# Sheet1.net
KiCad netlist of a schematic drawn in Altium Designer
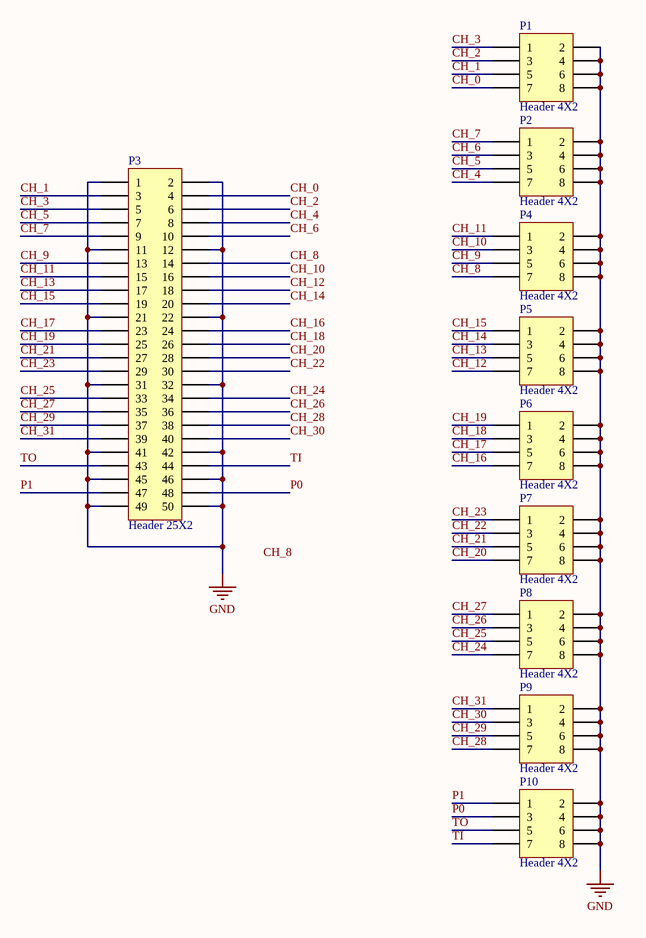
[diagram p0: Sheet1.SchDoc]

(export (version "E")
  (design (tool "Eeschema 10.0.6"))
  (components
    (comp (ref "P1")
      (value "Header 4X2")
      (footprint "HDR-2*4-1.27-SMD")
      (description "Header, 4-Pin, Dual row")
      (fields (field (name "PUBLISHER") "Altium Limited"))
      (libsource (lib "Miscellaneous Connectors") (part "Header 4X2"))
    )
    (comp (ref "P2")
      (value "Header 4X2")
      (footprint "HDR-2*4-1.27-SMD")
      (description "Header, 4-Pin, Dual row")
      (fields (field (name "PUBLISHER") "Altium Limited"))
      (libsource (lib "Miscellaneous Connectors") (part "Header 4X2"))
    )
    (comp (ref "P3")
      (value "Header 25X2")
      (footprint "HDR-2*25-2.54-SMD")
      (description "Header, 25-Pin, Dual row")
      (fields (field (name "PUBLISHER") "Altium Limited"))
      (libsource (lib "Miscellaneous Connectors") (part "Header 25X2"))
    )
    (comp (ref "P4")
      (value "Header 4X2")
      (footprint "HDR-2*4-1.27-SMD")
      (description "Header, 4-Pin, Dual row")
      (fields (field (name "PUBLISHER") "Altium Limited"))
      (libsource (lib "Miscellaneous Connectors") (part "Header 4X2"))
    )
    (comp (ref "P5")
      (value "Header 4X2")
      (footprint "HDR-2*4-1.27-SMD")
      (description "Header, 4-Pin, Dual row")
      (fields (field (name "PUBLISHER") "Altium Limited"))
      (libsource (lib "Miscellaneous Connectors") (part "Header 4X2"))
    )
    (comp (ref "P6")
      (value "Header 4X2")
      (footprint "HDR-2*4-1.27-SMD")
      (description "Header, 4-Pin, Dual row")
      (fields (field (name "PUBLISHER") "Altium Limited"))
      (libsource (lib "Miscellaneous Connectors") (part "Header 4X2"))
    )
    (comp (ref "P7")
      (value "Header 4X2")
      (footprint "HDR-2*4-1.27-SMD")
      (description "Header, 4-Pin, Dual row")
      (fields (field (name "PUBLISHER") "Altium Limited"))
      (libsource (lib "Miscellaneous Connectors") (part "Header 4X2"))
    )
    (comp (ref "P8")
      (value "Header 4X2")
      (footprint "HDR-2*4-1.27-SMD")
      (description "Header, 4-Pin, Dual row")
      (fields (field (name "PUBLISHER") "Altium Limited"))
      (libsource (lib "Miscellaneous Connectors") (part "Header 4X2"))
    )
    (comp (ref "P9")
      (value "Header 4X2")
      (footprint "HDR-2*4-1.27-SMD")
      (description "Header, 4-Pin, Dual row")
      (fields (field (name "PUBLISHER") "Altium Limited"))
      (libsource (lib "Miscellaneous Connectors") (part "Header 4X2"))
    )
    (comp (ref "P10")
      (value "Header 4X2")
      (footprint "HDR-2*4-1.27-SMD")
      (description "Header, 4-Pin, Dual row")
      (fields (field (name "PUBLISHER") "Altium Limited"))
      (libsource (lib "Miscellaneous Connectors") (part "Header 4X2"))
    )
  )
  (nets
    (net (code "1") (name "/CH_0") (class "Default")
      (node (ref "P1") (pin "7") (pinfunction "7_7") (pintype "passive"))
      (node (ref "P3") (pin "4") (pinfunction "4_4") (pintype "passive"))
    )
    (net (code "2") (name "/CH_1") (class "Default")
      (node (ref "P1") (pin "5") (pinfunction "5_5") (pintype "passive"))
      (node (ref "P3") (pin "3") (pinfunction "3_3") (pintype "passive"))
    )
    (net (code "3") (name "/CH_2") (class "Default")
      (node (ref "P1") (pin "3") (pinfunction "3_3") (pintype "passive"))
      (node (ref "P3") (pin "6") (pinfunction "6_6") (pintype "passive"))
    )
    (net (code "4") (name "/CH_3") (class "Default")
      (node (ref "P1") (pin "1") (pinfunction "1_1") (pintype "passive"))
      (node (ref "P3") (pin "5") (pinfunction "5_5") (pintype "passive"))
    )
    (net (code "5") (name "/CH_4") (class "Default")
      (node (ref "P2") (pin "7") (pinfunction "7_7") (pintype "passive"))
      (node (ref "P3") (pin "8") (pinfunction "8_8") (pintype "passive"))
    )
    (net (code "6") (name "/CH_5") (class "Default")
      (node (ref "P2") (pin "5") (pinfunction "5_5") (pintype "passive"))
      (node (ref "P3") (pin "7") (pinfunction "7_7") (pintype "passive"))
    )
    (net (code "7") (name "/CH_6") (class "Default")
      (node (ref "P2") (pin "3") (pinfunction "3_3") (pintype "passive"))
      (node (ref "P3") (pin "10") (pinfunction "10_10") (pintype "passive"))
    )
    (net (code "8") (name "/CH_7") (class "Default")
      (node (ref "P2") (pin "1") (pinfunction "1_1") (pintype "passive"))
      (node (ref "P3") (pin "9") (pinfunction "9_9") (pintype "passive"))
    )
    (net (code "9") (name "/CH_8") (class "Default")
      (node (ref "P3") (pin "14") (pinfunction "14_14") (pintype "passive"))
      (node (ref "P4") (pin "7") (pinfunction "7_7") (pintype "passive"))
    )
    (net (code "10") (name "/CH_9") (class "Default")
      (node (ref "P3") (pin "13") (pinfunction "13_13") (pintype "passive"))
      (node (ref "P4") (pin "5") (pinfunction "5_5") (pintype "passive"))
    )
    (net (code "11") (name "/CH_10") (class "Default")
      (node (ref "P3") (pin "16") (pinfunction "16_16") (pintype "passive"))
      (node (ref "P4") (pin "3") (pinfunction "3_3") (pintype "passive"))
    )
    (net (code "12") (name "/CH_11") (class "Default")
      (node (ref "P3") (pin "15") (pinfunction "15_15") (pintype "passive"))
      (node (ref "P4") (pin "1") (pinfunction "1_1") (pintype "passive"))
    )
    (net (code "13") (name "/CH_12") (class "Default")
      (node (ref "P3") (pin "18") (pinfunction "18_18") (pintype "passive"))
      (node (ref "P5") (pin "7") (pinfunction "7_7") (pintype "passive"))
    )
    (net (code "14") (name "/CH_13") (class "Default")
      (node (ref "P3") (pin "17") (pinfunction "17_17") (pintype "passive"))
      (node (ref "P5") (pin "5") (pinfunction "5_5") (pintype "passive"))
    )
    (net (code "15") (name "/CH_14") (class "Default")
      (node (ref "P3") (pin "20") (pinfunction "20_20") (pintype "passive"))
      (node (ref "P5") (pin "3") (pinfunction "3_3") (pintype "passive"))
    )
    (net (code "16") (name "/CH_15") (class "Default")
      (node (ref "P3") (pin "19") (pinfunction "19_19") (pintype "passive"))
      (node (ref "P5") (pin "1") (pinfunction "1_1") (pintype "passive"))
    )
    (net (code "17") (name "/CH_16") (class "Default")
      (node (ref "P3") (pin "24") (pinfunction "24_24") (pintype "passive"))
      (node (ref "P6") (pin "7") (pinfunction "7_7") (pintype "passive"))
    )
    (net (code "18") (name "/CH_17") (class "Default")
      (node (ref "P3") (pin "23") (pinfunction "23_23") (pintype "passive"))
      (node (ref "P6") (pin "5") (pinfunction "5_5") (pintype "passive"))
    )
    (net (code "19") (name "/CH_18") (class "Default")
      (node (ref "P3") (pin "26") (pinfunction "26_26") (pintype "passive"))
      (node (ref "P6") (pin "3") (pinfunction "3_3") (pintype "passive"))
    )
    (net (code "20") (name "/CH_19") (class "Default")
      (node (ref "P3") (pin "25") (pinfunction "25_25") (pintype "passive"))
      (node (ref "P6") (pin "1") (pinfunction "1_1") (pintype "passive"))
    )
    (net (code "21") (name "/CH_20") (class "Default")
      (node (ref "P3") (pin "28") (pinfunction "28_28") (pintype "passive"))
      (node (ref "P7") (pin "7") (pinfunction "7_7") (pintype "passive"))
    )
    (net (code "22") (name "/CH_21") (class "Default")
      (node (ref "P3") (pin "27") (pinfunction "27_27") (pintype "passive"))
      (node (ref "P7") (pin "5") (pinfunction "5_5") (pintype "passive"))
    )
    (net (code "23") (name "/CH_22") (class "Default")
      (node (ref "P3") (pin "30") (pinfunction "30_30") (pintype "passive"))
      (node (ref "P7") (pin "3") (pinfunction "3_3") (pintype "passive"))
    )
    (net (code "24") (name "/CH_23") (class "Default")
      (node (ref "P3") (pin "29") (pinfunction "29_29") (pintype "passive"))
      (node (ref "P7") (pin "1") (pinfunction "1_1") (pintype "passive"))
    )
    (net (code "25") (name "/CH_24") (class "Default")
      (node (ref "P3") (pin "34") (pinfunction "34_34") (pintype "passive"))
      (node (ref "P8") (pin "7") (pinfunction "7_7") (pintype "passive"))
    )
    (net (code "26") (name "/CH_25") (class "Default")
      (node (ref "P3") (pin "33") (pinfunction "33_33") (pintype "passive"))
      (node (ref "P8") (pin "5") (pinfunction "5_5") (pintype "passive"))
    )
    (net (code "27") (name "/CH_26") (class "Default")
      (node (ref "P3") (pin "36") (pinfunction "36_36") (pintype "passive"))
      (node (ref "P8") (pin "3") (pinfunction "3_3") (pintype "passive"))
    )
    (net (code "28") (name "/CH_27") (class "Default")
      (node (ref "P3") (pin "35") (pinfunction "35_35") (pintype "passive"))
      (node (ref "P8") (pin "1") (pinfunction "1_1") (pintype "passive"))
    )
    (net (code "29") (name "/CH_28") (class "Default")
      (node (ref "P3") (pin "38") (pinfunction "38_38") (pintype "passive"))
      (node (ref "P9") (pin "7") (pinfunction "7_7") (pintype "passive"))
    )
    (net (code "30") (name "/CH_29") (class "Default")
      (node (ref "P3") (pin "37") (pinfunction "37_37") (pintype "passive"))
      (node (ref "P9") (pin "5") (pinfunction "5_5") (pintype "passive"))
    )
    (net (code "31") (name "/CH_30") (class "Default")
      (node (ref "P3") (pin "40") (pinfunction "40_40") (pintype "passive"))
      (node (ref "P9") (pin "3") (pinfunction "3_3") (pintype "passive"))
    )
    (net (code "32") (name "/CH_31") (class "Default")
      (node (ref "P3") (pin "39") (pinfunction "39_39") (pintype "passive"))
      (node (ref "P9") (pin "1") (pinfunction "1_1") (pintype "passive"))
    )
    (net (code "33") (name "/P0") (class "Default")
      (node (ref "P10") (pin "3") (pinfunction "3_3") (pintype "passive"))
      (node (ref "P3") (pin "48") (pinfunction "48_48") (pintype "passive"))
    )
    (net (code "34") (name "/P1") (class "Default")
      (node (ref "P10") (pin "1") (pinfunction "1_1") (pintype "passive"))
      (node (ref "P3") (pin "47") (pinfunction "47_47") (pintype "passive"))
    )
    (net (code "35") (name "/TI") (class "Default")
      (node (ref "P10") (pin "7") (pinfunction "7_7") (pintype "passive"))
      (node (ref "P3") (pin "44") (pinfunction "44_44") (pintype "passive"))
    )
    (net (code "36") (name "/TO") (class "Default")
      (node (ref "P10") (pin "5") (pinfunction "5_5") (pintype "passive"))
      (node (ref "P3") (pin "43") (pinfunction "43_43") (pintype "passive"))
    )
    (net (code "37") (name "GND") (class "Default")
      (node (ref "P1") (pin "2") (pinfunction "2_2") (pintype "passive"))
      (node (ref "P1") (pin "4") (pinfunction "4_4") (pintype "passive"))
      (node (ref "P1") (pin "6") (pinfunction "6_6") (pintype "passive"))
      (node (ref "P1") (pin "8") (pinfunction "8_8") (pintype "passive"))
      (node (ref "P10") (pin "2") (pinfunction "2_2") (pintype "passive"))
      (node (ref "P10") (pin "4") (pinfunction "4_4") (pintype "passive"))
      (node (ref "P10") (pin "6") (pinfunction "6_6") (pintype "passive"))
      (node (ref "P10") (pin "8") (pinfunction "8_8") (pintype "passive"))
      (node (ref "P2") (pin "2") (pinfunction "2_2") (pintype "passive"))
      (node (ref "P2") (pin "4") (pinfunction "4_4") (pintype "passive"))
      (node (ref "P2") (pin "6") (pinfunction "6_6") (pintype "passive"))
      (node (ref "P2") (pin "8") (pinfunction "8_8") (pintype "passive"))
      (node (ref "P3") (pin "1") (pinfunction "1_1") (pintype "passive"))
      (node (ref "P3") (pin "11") (pinfunction "11_11") (pintype "passive"))
      (node (ref "P3") (pin "12") (pinfunction "12_12") (pintype "passive"))
      (node (ref "P3") (pin "2") (pinfunction "2_2") (pintype "passive"))
      (node (ref "P3") (pin "21") (pinfunction "21_21") (pintype "passive"))
      (node (ref "P3") (pin "22") (pinfunction "22_22") (pintype "passive"))
      (node (ref "P3") (pin "31") (pinfunction "31_31") (pintype "passive"))
      (node (ref "P3") (pin "32") (pinfunction "32_32") (pintype "passive"))
      (node (ref "P3") (pin "41") (pinfunction "41_41") (pintype "passive"))
      (node (ref "P3") (pin "42") (pinfunction "42_42") (pintype "passive"))
      (node (ref "P3") (pin "45") (pinfunction "45_45") (pintype "passive"))
      (node (ref "P3") (pin "46") (pinfunction "46_46") (pintype "passive"))
      (node (ref "P3") (pin "49") (pinfunction "49_49") (pintype "passive"))
      (node (ref "P3") (pin "50") (pinfunction "50_50") (pintype "passive"))
      (node (ref "P4") (pin "2") (pinfunction "2_2") (pintype "passive"))
      (node (ref "P4") (pin "4") (pinfunction "4_4") (pintype "passive"))
      (node (ref "P4") (pin "6") (pinfunction "6_6") (pintype "passive"))
      (node (ref "P4") (pin "8") (pinfunction "8_8") (pintype "passive"))
      (node (ref "P5") (pin "2") (pinfunction "2_2") (pintype "passive"))
      (node (ref "P5") (pin "4") (pinfunction "4_4") (pintype "passive"))
      (node (ref "P5") (pin "6") (pinfunction "6_6") (pintype "passive"))
      (node (ref "P5") (pin "8") (pinfunction "8_8") (pintype "passive"))
      (node (ref "P6") (pin "2") (pinfunction "2_2") (pintype "passive"))
      (node (ref "P6") (pin "4") (pinfunction "4_4") (pintype "passive"))
      (node (ref "P6") (pin "6") (pinfunction "6_6") (pintype "passive"))
      (node (ref "P6") (pin "8") (pinfunction "8_8") (pintype "passive"))
      (node (ref "P7") (pin "2") (pinfunction "2_2") (pintype "passive"))
      (node (ref "P7") (pin "4") (pinfunction "4_4") (pintype "passive"))
      (node (ref "P7") (pin "6") (pinfunction "6_6") (pintype "passive"))
      (node (ref "P7") (pin "8") (pinfunction "8_8") (pintype "passive"))
      (node (ref "P8") (pin "2") (pinfunction "2_2") (pintype "passive"))
      (node (ref "P8") (pin "4") (pinfunction "4_4") (pintype "passive"))
      (node (ref "P8") (pin "6") (pinfunction "6_6") (pintype "passive"))
      (node (ref "P8") (pin "8") (pinfunction "8_8") (pintype "passive"))
      (node (ref "P9") (pin "2") (pinfunction "2_2") (pintype "passive"))
      (node (ref "P9") (pin "4") (pinfunction "4_4") (pintype "passive"))
      (node (ref "P9") (pin "6") (pinfunction "6_6") (pintype "passive"))
      (node (ref "P9") (pin "8") (pinfunction "8_8") (pintype "passive"))
    )
  )
)
